# OurEDA-P1K_zynq.net
KiCad netlist of a schematic drawn in Altium Designer
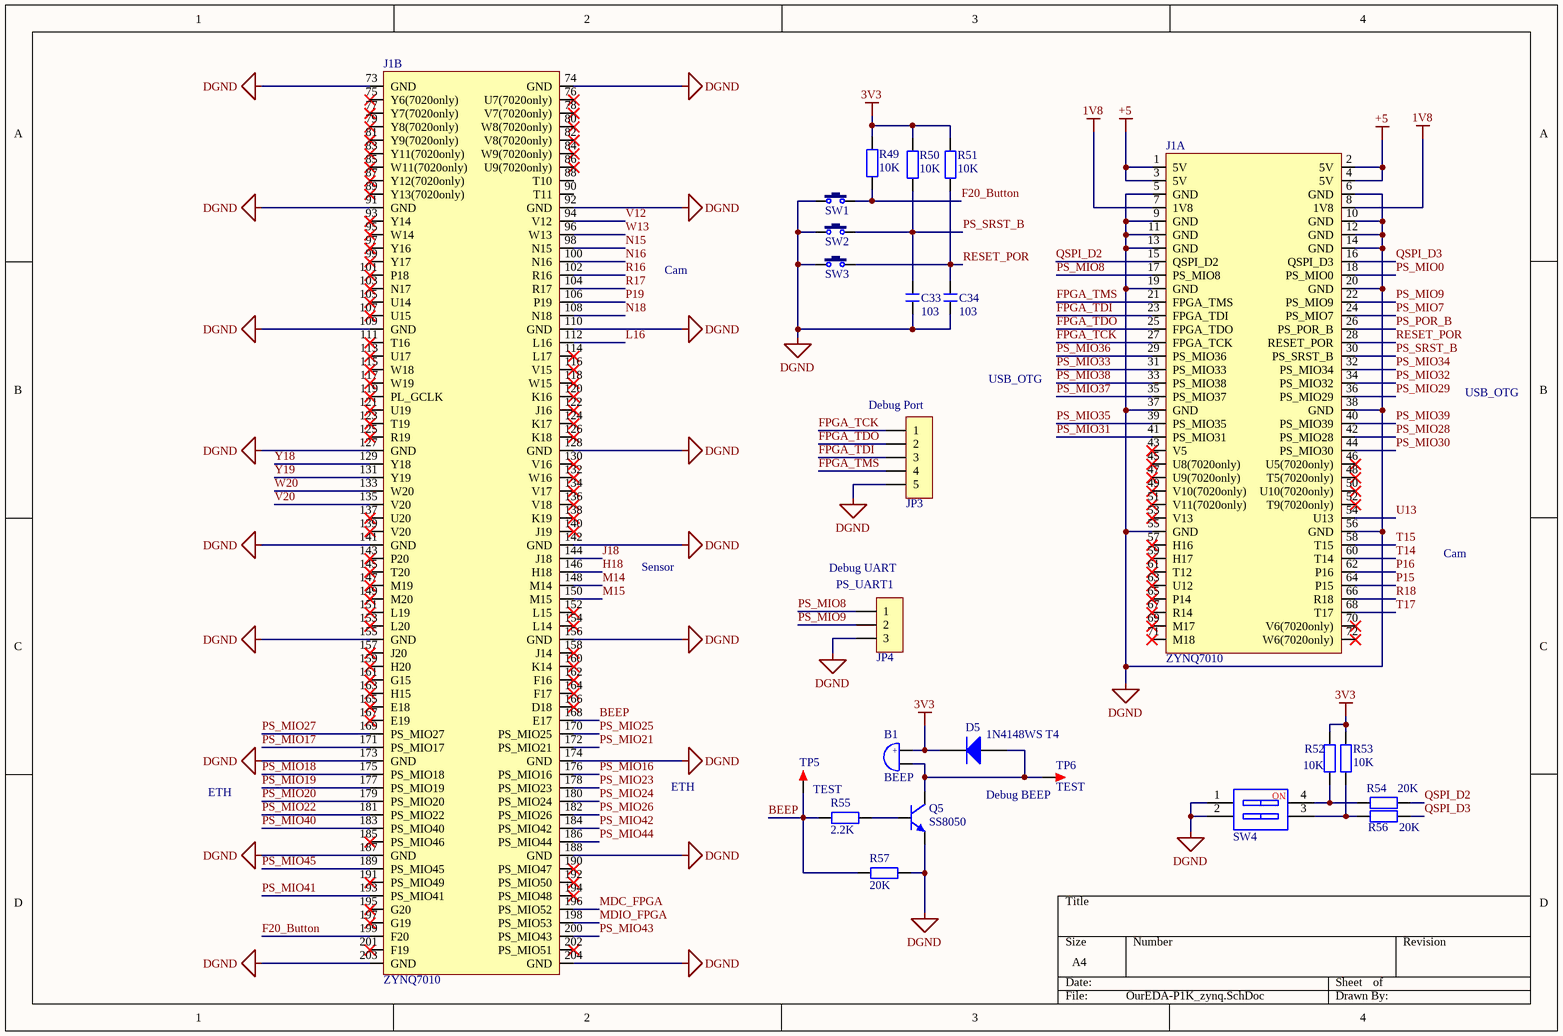
[diagram p0: OurEDA-P1K_zynq.SchDoc]

(export (version "E")
  (design (tool "Eeschema 10.0.6"))
  (components
    (comp (ref "B1")
      (value "BEEP")
      (footprint "BEEP 5x9x5.5")
      (description "蜂鸣器")
      (libsource (lib "蜂鸣器") (part "BEEP"))
    )
    (comp (ref "C33")
      (value "103")
      (footprint "C 0603_L")
      (description "无极性贴片电容")
      (fields (field (name "版权归属") "源创客"))
      (libsource (lib "3.1   - 电阻-电容-电感") (part "C"))
    )
    (comp (ref "C34")
      (value "103")
      (footprint "C 0603_L")
      (description "无极性贴片电容")
      (fields (field (name "版权归属") "源创客"))
      (libsource (lib "3.1   - 电阻-电容-电感") (part "C"))
    )
    (comp (ref "D5")
      (value "1N4148WS T4")
      (footprint "SOD-323")
      (description "二极管")
      (libsource (lib "Miscellaneous Devices LC") (part "SOD-323 1N4148WS T4"))
    )
    (comp (ref "J1")
      (value "ZYNQ7010")
      (footprint "DDR3_sodimm_Pin204")
      (libsource (lib "MySchLib") (part "DDR3_sodimm_Pin204"))
    )
    (comp (ref "JP3")
      (value "HDR-1X5")
      (footprint "MX 1.25-LS-5P")
      (description "5P接插件")
      (fields (field (name "版权归属") "源创客"))
      (libsource (lib "4.2   - 接插件-脚距1.25") (part "Header 5"))
    )
    (comp (ref "JP4")
      (value "HDR-1X3")
      (footprint "MX 1.25-LS-3P")
      (description "3P接插件")
      (fields (field (name "版权归属") "源创客"))
      (libsource (lib "4.2   - 接插件-脚距1.25") (part "Header 3"))
    )
    (comp (ref "Q5")
      (value "SS8050")
      (footprint "SOT23-3N")
      (description "高频放大-NPN型")
      (fields (field (name "版权归属") "源创客"))
      (libsource (lib "6.2   - 三极管") (part "8050-SMD"))
    )
    (comp (ref "R49")
      (value "10K")
      (footprint "R 0603_L")
      (description "贴片电阻")
      (fields (field (name "版权归属") "源创客"))
      (libsource (lib "3.1   - 电阻-电容-电感") (part "R"))
    )
    (comp (ref "R50")
      (value "10K")
      (footprint "R 0603_L")
      (description "贴片电阻")
      (fields (field (name "版权归属") "源创客"))
      (libsource (lib "3.1   - 电阻-电容-电感") (part "R"))
    )
    (comp (ref "R51")
      (value "10K")
      (footprint "R 0603_L")
      (description "贴片电阻")
      (fields (field (name "版权归属") "源创客"))
      (libsource (lib "3.1   - 电阻-电容-电感") (part "R"))
    )
    (comp (ref "R52")
      (value "10K")
      (footprint "R 0603_L")
      (description "贴片电阻")
      (fields (field (name "版权归属") "源创客"))
      (libsource (lib "3.1   - 电阻-电容-电感") (part "R"))
    )
    (comp (ref "R53")
      (value "10K")
      (footprint "R 0603_L")
      (description "贴片电阻")
      (fields (field (name "版权归属") "源创客"))
      (libsource (lib "3.1   - 电阻-电容-电感") (part "R"))
    )
    (comp (ref "R54")
      (value "20K")
      (footprint "R 0603_L")
      (description "贴片电阻")
      (fields (field (name "版权归属") "源创客"))
      (libsource (lib "3.1   - 电阻-电容-电感") (part "R"))
    )
    (comp (ref "R55")
      (value "2.2K")
      (footprint "R 0603_L")
      (description "贴片电阻")
      (fields (field (name "版权归属") "源创客"))
      (libsource (lib "3.1   - 电阻-电容-电感") (part "R"))
    )
    (comp (ref "R56")
      (value "20K")
      (footprint "R 0603_L")
      (description "贴片电阻")
      (fields (field (name "版权归属") "源创客"))
      (libsource (lib "3.1   - 电阻-电容-电感") (part "R"))
    )
    (comp (ref "R57")
      (value "20K")
      (footprint "R 0603_L")
      (description "贴片电阻")
      (fields (field (name "版权归属") "源创客"))
      (libsource (lib "3.1   - 电阻-电容-电感") (part "R"))
    )
    (comp (ref "SW1")
      (value "3x6x5")
      (footprint "TSW SMD-3*6*2.5")
      (description "3x6轻触开关")
      (fields (field (name "版权归属") "源创客"))
      (libsource (lib "5.1   - 按键-开关") (part "TSW 3x6"))
    )
    (comp (ref "SW2")
      (value "3x6x5")
      (footprint "TSW SMD-3*6*2.5")
      (description "3x6轻触开关")
      (fields (field (name "版权归属") "源创客"))
      (libsource (lib "5.1   - 按键-开关") (part "TSW 3x6"))
    )
    (comp (ref "SW3")
      (value "3x6x5")
      (footprint "TSW SMD-3*6*2.5")
      (description "3x6轻触开关")
      (fields (field (name "版权归属") "源创客"))
      (libsource (lib "5.1   - 按键-开关") (part "TSW 3x6"))
    )
    (comp (ref "SW4")
      (value "CSW-2P")
      (footprint "CSW1.27 SMD-2P")
      (description "2路编码开关")
      (fields (field (name "版权归属") "源创客"))
      (libsource (lib "5.1   - 按键-开关") (part "CSW-2P"))
    )
    (comp (ref "TP5")
      (value "TEST")
      (footprint "TEST 1")
      (description "测试点")
      (fields (field (name "版权归属") "源创客"))
      (libsource (lib "15.1 - 未分类器件") (part "TEST"))
    )
    (comp (ref "TP6")
      (value "TEST")
      (footprint "TEST 1")
      (description "测试点")
      (fields (field (name "版权归属") "源创客"))
      (libsource (lib "15.1 - 未分类器件") (part "TEST"))
    )
  )
  (nets
    (net (code "1") (name "+5") (class "Default")
      (node (ref "J1") (pin "1") (pinfunction "5V_1") (pintype "passive"))
      (node (ref "J1") (pin "2") (pinfunction "5V_2") (pintype "passive"))
      (node (ref "J1") (pin "3") (pinfunction "5V_3") (pintype "passive"))
      (node (ref "J1") (pin "4") (pinfunction "5V_4") (pintype "passive"))
    )
    (net (code "2") (name "/BEEP") (class "Default")
      (node (ref "J1") (pin "168") (pinfunction "E17_168") (pintype "passive"))
      (node (ref "R55") (pin "2") (pinfunction "2_2") (pintype "passive"))
      (node (ref "R57") (pin "1") (pinfunction "1_1") (pintype "passive"))
      (node (ref "TP5") (pin "1") (pinfunction "1_1") (pintype "passive"))
    )
    (net (code "3") (name "/F20_Button") (class "Default")
      (node (ref "J1") (pin "199") (pinfunction "F20_199") (pintype "passive"))
      (node (ref "R49") (pin "1") (pinfunction "1_1") (pintype "passive"))
      (node (ref "SW1") (pin "2") (pinfunction "2_2") (pintype "passive"))
    )
    (net (code "4") (name "/FPGA_TCK") (class "Default")
      (node (ref "J1") (pin "27") (pinfunction "FPGA_TCK_27") (pintype "passive"))
      (node (ref "JP3") (pin "1") (pinfunction "1_1") (pintype "passive"))
    )
    (net (code "5") (name "/FPGA_TDI") (class "Default")
      (node (ref "J1") (pin "23") (pinfunction "FPGA_TDI_23") (pintype "passive"))
      (node (ref "JP3") (pin "3") (pinfunction "3_3") (pintype "passive"))
    )
    (net (code "6") (name "/FPGA_TDO") (class "Default")
      (node (ref "J1") (pin "25") (pinfunction "FPGA_TDO_25") (pintype "passive"))
      (node (ref "JP3") (pin "2") (pinfunction "2_2") (pintype "passive"))
    )
    (net (code "7") (name "/FPGA_TMS") (class "Default")
      (node (ref "J1") (pin "21") (pinfunction "FPGA_TMS_21") (pintype "passive"))
      (node (ref "JP3") (pin "4") (pinfunction "4_4") (pintype "passive"))
    )
    (net (code "8") (name "/H18") (class "Default")
      (node (ref "J1") (pin "146") (pinfunction "H18_146") (pintype "passive"))
    )
    (net (code "9") (name "/J18") (class "Default")
      (node (ref "J1") (pin "144") (pinfunction "J18_144") (pintype "passive"))
    )
    (net (code "10") (name "/L16") (class "Default")
      (node (ref "J1") (pin "112") (pinfunction "L16_112") (pintype "passive"))
    )
    (net (code "11") (name "/M14") (class "Default")
      (node (ref "J1") (pin "148") (pinfunction "M14_148") (pintype "passive"))
    )
    (net (code "12") (name "/M15") (class "Default")
      (node (ref "J1") (pin "150") (pinfunction "M15_150") (pintype "passive"))
    )
    (net (code "13") (name "/MDC_FPGA") (class "Default")
      (node (ref "J1") (pin "196") (pinfunction "PS_MIO52_196") (pintype "passive"))
    )
    (net (code "14") (name "/MDIO_FPGA") (class "Default")
      (node (ref "J1") (pin "198") (pinfunction "PS_MIO53_198") (pintype "passive"))
    )
    (net (code "15") (name "/N15") (class "Default")
      (node (ref "J1") (pin "98") (pinfunction "N15_98") (pintype "passive"))
    )
    (net (code "16") (name "/N16") (class "Default")
      (node (ref "J1") (pin "100") (pinfunction "N16_100") (pintype "passive"))
    )
    (net (code "17") (name "/N18") (class "Default")
      (node (ref "J1") (pin "108") (pinfunction "N18_108") (pintype "passive"))
    )
    (net (code "18") (name "/P15") (class "Default")
      (node (ref "J1") (pin "64") (pinfunction "P15_64") (pintype "passive"))
    )
    (net (code "19") (name "/P16") (class "Default")
      (node (ref "J1") (pin "62") (pinfunction "P16_62") (pintype "passive"))
    )
    (net (code "20") (name "/P19") (class "Default")
      (node (ref "J1") (pin "106") (pinfunction "P19_106") (pintype "passive"))
    )
    (net (code "21") (name "/PS_MIO0") (class "Default")
      (node (ref "J1") (pin "18") (pinfunction "PS_MIO0_18") (pintype "passive"))
    )
    (net (code "22") (name "/PS_MIO7") (class "Default")
      (node (ref "J1") (pin "24") (pinfunction "PS_MIO7_24") (pintype "passive"))
    )
    (net (code "23") (name "/PS_MIO8") (class "Default")
      (node (ref "J1") (pin "17") (pinfunction "PS_MIO8_17") (pintype "passive"))
      (node (ref "JP4") (pin "1") (pinfunction "1_1") (pintype "passive"))
    )
    (net (code "24") (name "/PS_MIO9") (class "Default")
      (node (ref "J1") (pin "22") (pinfunction "PS_MIO9_22") (pintype "passive"))
      (node (ref "JP4") (pin "2") (pinfunction "2_2") (pintype "passive"))
    )
    (net (code "25") (name "/PS_MIO16") (class "Default")
      (node (ref "J1") (pin "176") (pinfunction "PS_MIO16_176") (pintype "passive"))
    )
    (net (code "26") (name "/PS_MIO17") (class "Default")
      (node (ref "J1") (pin "171") (pinfunction "PS_MIO17_171") (pintype "passive"))
    )
    (net (code "27") (name "/PS_MIO18") (class "Default")
      (node (ref "J1") (pin "175") (pinfunction "PS_MIO18_175") (pintype "passive"))
    )
    (net (code "28") (name "/PS_MIO19") (class "Default")
      (node (ref "J1") (pin "177") (pinfunction "PS_MIO19_177") (pintype "passive"))
    )
    (net (code "29") (name "/PS_MIO20") (class "Default")
      (node (ref "J1") (pin "179") (pinfunction "PS_MIO20_179") (pintype "passive"))
    )
    (net (code "30") (name "/PS_MIO21") (class "Default")
      (node (ref "J1") (pin "172") (pinfunction "PS_MIO21_172") (pintype "passive"))
    )
    (net (code "31") (name "/PS_MIO22") (class "Default")
      (node (ref "J1") (pin "181") (pinfunction "PS_MIO22_181") (pintype "passive"))
    )
    (net (code "32") (name "/PS_MIO23") (class "Default")
      (node (ref "J1") (pin "178") (pinfunction "PS_MIO23_178") (pintype "passive"))
    )
    (net (code "33") (name "/PS_MIO24") (class "Default")
      (node (ref "J1") (pin "180") (pinfunction "PS_MIO24_180") (pintype "passive"))
    )
    (net (code "34") (name "/PS_MIO25") (class "Default")
      (node (ref "J1") (pin "170") (pinfunction "PS_MIO25_170") (pintype "passive"))
    )
    (net (code "35") (name "/PS_MIO26") (class "Default")
      (node (ref "J1") (pin "182") (pinfunction "PS_MIO26_182") (pintype "passive"))
    )
    (net (code "36") (name "/PS_MIO27") (class "Default")
      (node (ref "J1") (pin "169") (pinfunction "PS_MIO27_169") (pintype "passive"))
    )
    (net (code "37") (name "/PS_MIO28") (class "Default")
      (node (ref "J1") (pin "42") (pinfunction "PS_MIO28_42") (pintype "passive"))
    )
    (net (code "38") (name "/PS_MIO29") (class "Default")
      (node (ref "J1") (pin "36") (pinfunction "PS_MIO29_36") (pintype "passive"))
    )
    (net (code "39") (name "/PS_MIO30") (class "Default")
      (node (ref "J1") (pin "44") (pinfunction "PS_MIO30_44") (pintype "passive"))
    )
    (net (code "40") (name "/PS_MIO31") (class "Default")
      (node (ref "J1") (pin "41") (pinfunction "PS_MIO31_41") (pintype "passive"))
    )
    (net (code "41") (name "/PS_MIO32") (class "Default")
      (node (ref "J1") (pin "34") (pinfunction "PS_MIO32_34") (pintype "passive"))
    )
    (net (code "42") (name "/PS_MIO33") (class "Default")
      (node (ref "J1") (pin "31") (pinfunction "PS_MIO33_31") (pintype "passive"))
    )
    (net (code "43") (name "/PS_MIO34") (class "Default")
      (node (ref "J1") (pin "32") (pinfunction "PS_MIO34_32") (pintype "passive"))
    )
    (net (code "44") (name "/PS_MIO35") (class "Default")
      (node (ref "J1") (pin "39") (pinfunction "PS_MIO35_39") (pintype "passive"))
    )
    (net (code "45") (name "/PS_MIO36") (class "Default")
      (node (ref "J1") (pin "29") (pinfunction "PS_MIO36_29") (pintype "passive"))
    )
    (net (code "46") (name "/PS_MIO37") (class "Default")
      (node (ref "J1") (pin "35") (pinfunction "PS_MIO37_35") (pintype "passive"))
    )
    (net (code "47") (name "/PS_MIO38") (class "Default")
      (node (ref "J1") (pin "33") (pinfunction "PS_MIO38_33") (pintype "passive"))
    )
    (net (code "48") (name "/PS_MIO39") (class "Default")
      (node (ref "J1") (pin "40") (pinfunction "PS_MIO39_40") (pintype "passive"))
    )
    (net (code "49") (name "/PS_MIO40") (class "Default")
      (node (ref "J1") (pin "183") (pinfunction "PS_MIO40_183") (pintype "passive"))
    )
    (net (code "50") (name "/PS_MIO41") (class "Default")
      (node (ref "J1") (pin "193") (pinfunction "PS_MIO41_193") (pintype "passive"))
    )
    (net (code "51") (name "/PS_MIO42") (class "Default")
      (node (ref "J1") (pin "184") (pinfunction "PS_MIO42_184") (pintype "passive"))
    )
    (net (code "52") (name "/PS_MIO43") (class "Default")
      (node (ref "J1") (pin "200") (pinfunction "PS_MIO43_200") (pintype "passive"))
    )
    (net (code "53") (name "/PS_MIO44") (class "Default")
      (node (ref "J1") (pin "186") (pinfunction "PS_MIO44_186") (pintype "passive"))
    )
    (net (code "54") (name "/PS_MIO45") (class "Default")
      (node (ref "J1") (pin "189") (pinfunction "PS_MIO45_189") (pintype "passive"))
    )
    (net (code "55") (name "/PS_POR_B") (class "Default")
      (node (ref "J1") (pin "26") (pinfunction "PS_POR_B_26") (pintype "passive"))
    )
    (net (code "56") (name "/PS_SRST_B") (class "Default")
      (node (ref "C33") (pin "2") (pinfunction "2_2") (pintype "passive"))
      (node (ref "J1") (pin "30") (pinfunction "PS_SRST_B_30") (pintype "passive"))
      (node (ref "R50") (pin "1") (pinfunction "1_1") (pintype "passive"))
      (node (ref "SW2") (pin "2") (pinfunction "2_2") (pintype "passive"))
    )
    (net (code "57") (name "/QSPI_D2") (class "Default")
      (node (ref "J1") (pin "15") (pinfunction "QSPI_D2_15") (pintype "passive"))
      (node (ref "R54") (pin "2") (pinfunction "2_2") (pintype "passive"))
    )
    (net (code "58") (name "/QSPI_D3") (class "Default")
      (node (ref "J1") (pin "16") (pinfunction "QSPI_D3_16") (pintype "passive"))
      (node (ref "R56") (pin "2") (pinfunction "2_2") (pintype "passive"))
    )
    (net (code "59") (name "/R16") (class "Default")
      (node (ref "J1") (pin "102") (pinfunction "R16_102") (pintype "passive"))
    )
    (net (code "60") (name "/R17") (class "Default")
      (node (ref "J1") (pin "104") (pinfunction "R17_104") (pintype "passive"))
    )
    (net (code "61") (name "/R18") (class "Default")
      (node (ref "J1") (pin "66") (pinfunction "R18_66") (pintype "passive"))
    )
    (net (code "62") (name "/RESET_POR") (class "Default")
      (node (ref "C34") (pin "2") (pinfunction "2_2") (pintype "passive"))
      (node (ref "J1") (pin "28") (pinfunction "RESET_POR_28") (pintype "passive"))
      (node (ref "R51") (pin "1") (pinfunction "1_1") (pintype "passive"))
      (node (ref "SW3") (pin "2") (pinfunction "2_2") (pintype "passive"))
    )
    (net (code "63") (name "/T14") (class "Default")
      (node (ref "J1") (pin "60") (pinfunction "T14_60") (pintype "passive"))
    )
    (net (code "64") (name "/T15") (class "Default")
      (node (ref "J1") (pin "58") (pinfunction "T15_58") (pintype "passive"))
    )
    (net (code "65") (name "/T17") (class "Default")
      (node (ref "J1") (pin "68") (pinfunction "T17_68") (pintype "passive"))
    )
    (net (code "66") (name "/U13") (class "Default")
      (node (ref "J1") (pin "54") (pinfunction "U13_54") (pintype "passive"))
    )
    (net (code "67") (name "/V12") (class "Default")
      (node (ref "J1") (pin "94") (pinfunction "V12_94") (pintype "passive"))
    )
    (net (code "68") (name "/V20") (class "Default")
      (node (ref "J1") (pin "135") (pinfunction "V20_135") (pintype "passive"))
    )
    (net (code "69") (name "/W13") (class "Default")
      (node (ref "J1") (pin "96") (pinfunction "W13_96") (pintype "passive"))
    )
    (net (code "70") (name "/W20") (class "Default")
      (node (ref "J1") (pin "133") (pinfunction "W20_133") (pintype "passive"))
    )
    (net (code "71") (name "/Y18") (class "Default")
      (node (ref "J1") (pin "129") (pinfunction "Y18_129") (pintype "passive"))
    )
    (net (code "72") (name "/Y19") (class "Default")
      (node (ref "J1") (pin "131") (pinfunction "Y19_131") (pintype "passive"))
    )
    (net (code "73") (name "1V8") (class "Default")
      (node (ref "J1") (pin "7") (pinfunction "1V8_7") (pintype "passive"))
      (node (ref "J1") (pin "8") (pinfunction "1V8_8") (pintype "passive"))
    )
    (net (code "74") (name "3V3") (class "Default")
      (node (ref "B1") (pin "1") (pinfunction "1_1") (pintype "passive"))
      (node (ref "D5") (pin "2") (pinfunction "K_2") (pintype "passive"))
      (node (ref "R49") (pin "2") (pinfunction "2_2") (pintype "passive"))
      (node (ref "R50") (pin "2") (pinfunction "2_2") (pintype "passive"))
      (node (ref "R51") (pin "2") (pinfunction "2_2") (pintype "passive"))
      (node (ref "R52") (pin "2") (pinfunction "2_2") (pintype "passive"))
      (node (ref "R53") (pin "2") (pinfunction "2_2") (pintype "passive"))
    )
    (net (code "75") (name "DGND") (class "Default")
      (node (ref "C33") (pin "1") (pinfunction "1_1") (pintype "passive"))
      (node (ref "C34") (pin "1") (pinfunction "1_1") (pintype "passive"))
      (node (ref "J1") (pin "10") (pinfunction "GND_10") (pintype "passive"))
      (node (ref "J1") (pin "109") (pinfunction "GND_109") (pintype "passive"))
      (node (ref "J1") (pin "11") (pinfunction "GND_11") (pintype "passive"))
      (node (ref "J1") (pin "110") (pinfunction "GND_110") (pintype "passive"))
      (node (ref "J1") (pin "12") (pinfunction "GND_12") (pintype "passive"))
      (node (ref "J1") (pin "127") (pinfunction "GND_127") (pintype "passive"))
      (node (ref "J1") (pin "128") (pinfunction "GND_128") (pintype "passive"))
      (node (ref "J1") (pin "13") (pinfunction "GND_13") (pintype "passive"))
      (node (ref "J1") (pin "14") (pinfunction "GND_14") (pintype "passive"))
      (node (ref "J1") (pin "141") (pinfunction "GND_141") (pintype "passive"))
      (node (ref "J1") (pin "142") (pinfunction "GND_142") (pintype "passive"))
      (node (ref "J1") (pin "155") (pinfunction "GND_155") (pintype "passive"))
      (node (ref "J1") (pin "156") (pinfunction "GND_156") (pintype "passive"))
      (node (ref "J1") (pin "173") (pinfunction "GND_173") (pintype "passive"))
      (node (ref "J1") (pin "174") (pinfunction "GND_174") (pintype "passive"))
      (node (ref "J1") (pin "187") (pinfunction "GND_187") (pintype "passive"))
      (node (ref "J1") (pin "188") (pinfunction "GND_188") (pintype "passive"))
      (node (ref "J1") (pin "19") (pinfunction "GND_19") (pintype "passive"))
      (node (ref "J1") (pin "20") (pinfunction "GND_20") (pintype "passive"))
      (node (ref "J1") (pin "203") (pinfunction "GND_203") (pintype "passive"))
      (node (ref "J1") (pin "204") (pinfunction "GND_204") (pintype "passive"))
      (node (ref "J1") (pin "37") (pinfunction "GND_37") (pintype "passive"))
      (node (ref "J1") (pin "38") (pinfunction "GND_38") (pintype "passive"))
      (node (ref "J1") (pin "5") (pinfunction "GND_5") (pintype "passive"))
      (node (ref "J1") (pin "55") (pinfunction "GND_55") (pintype "passive"))
      (node (ref "J1") (pin "56") (pinfunction "GND_56") (pintype "passive"))
      (node (ref "J1") (pin "6") (pinfunction "GND_6") (pintype "passive"))
      (node (ref "J1") (pin "73") (pinfunction "GND_73") (pintype "passive"))
      (node (ref "J1") (pin "74") (pinfunction "GND_74") (pintype "passive"))
      (node (ref "J1") (pin "9") (pinfunction "GND_9") (pintype "passive"))
      (node (ref "J1") (pin "91") (pinfunction "GND_91") (pintype "passive"))
      (node (ref "J1") (pin "92") (pinfunction "GND_92") (pintype "passive"))
      (node (ref "JP3") (pin "5") (pinfunction "5_5") (pintype "passive"))
      (node (ref "JP4") (pin "3") (pinfunction "3_3") (pintype "passive"))
      (node (ref "Q5") (pin "2") (pinfunction "E_2") (pintype "passive"))
      (node (ref "R57") (pin "2") (pinfunction "2_2") (pintype "passive"))
      (node (ref "SW1") (pin "1") (pinfunction "1_1") (pintype "passive"))
      (node (ref "SW2") (pin "1") (pinfunction "1_1") (pintype "passive"))
      (node (ref "SW3") (pin "1") (pinfunction "1_1") (pintype "passive"))
      (node (ref "SW4") (pin "1") (pinfunction "1_1") (pintype "passive"))
      (node (ref "SW4") (pin "2") (pinfunction "2_2") (pintype "passive"))
    )
    (net (code "76") (name "Net-(D5-A)") (class "Default")
      (node (ref "B1") (pin "2") (pinfunction "2_2") (pintype "passive"))
      (node (ref "D5") (pin "1") (pinfunction "A_1") (pintype "passive"))
      (node (ref "Q5") (pin "3") (pinfunction "C_3") (pintype "passive"))
      (node (ref "TP6") (pin "1") (pinfunction "1_1") (pintype "passive"))
    )
    (net (code "77") (name "Net-(Q5-B)") (class "Default")
      (node (ref "Q5") (pin "1") (pinfunction "B_1") (pintype "passive"))
      (node (ref "R55") (pin "1") (pinfunction "1_1") (pintype "passive"))
    )
    (net (code "78") (name "Net-(R52-Pad1)") (class "Default")
      (node (ref "R52") (pin "1") (pinfunction "1_1") (pintype "passive"))
      (node (ref "R54") (pin "1") (pinfunction "1_1") (pintype "passive"))
      (node (ref "SW4") (pin "4") (pinfunction "4_4") (pintype "passive"))
    )
    (net (code "79") (name "Net-(R53-Pad1)") (class "Default")
      (node (ref "R53") (pin "1") (pinfunction "1_1") (pintype "passive"))
      (node (ref "R56") (pin "1") (pinfunction "1_1") (pintype "passive"))
      (node (ref "SW4") (pin "3") (pinfunction "3_3") (pintype "passive"))
    )
    (net (code "80") (name "unconnected-(J1A-H16-Pad57)") (class "Default")
      (node (ref "J1") (pin "57") (pinfunction "H16_57") (pintype "passive+no_connect"))
    )
    (net (code "81") (name "unconnected-(J1A-H17-Pad59)") (class "Default")
      (node (ref "J1") (pin "59") (pinfunction "H17_59") (pintype "passive+no_connect"))
    )
    (net (code "82") (name "unconnected-(J1A-M17-Pad69)") (class "Default")
      (node (ref "J1") (pin "69") (pinfunction "M17_69") (pintype "passive+no_connect"))
    )
    (net (code "83") (name "unconnected-(J1A-M18-Pad71)") (class "Default")
      (node (ref "J1") (pin "71") (pinfunction "M18_71") (pintype "passive+no_connect"))
    )
    (net (code "84") (name "unconnected-(J1A-P14-Pad65)") (class "Default")
      (node (ref "J1") (pin "65") (pinfunction "P14_65") (pintype "passive+no_connect"))
    )
    (net (code "85") (name "unconnected-(J1A-R14-Pad67)") (class "Default")
      (node (ref "J1") (pin "67") (pinfunction "R14_67") (pintype "passive+no_connect"))
    )
    (net (code "86") (name "unconnected-(J1A-T5(7020only)-Pad48)") (class "Default")
      (node (ref "J1") (pin "48") (pinfunction "T5(7020only)_48") (pintype "passive+no_connect"))
    )
    (net (code "87") (name "unconnected-(J1A-T9(7020only)-Pad52)") (class "Default")
      (node (ref "J1") (pin "52") (pinfunction "T9(7020only)_52") (pintype "passive+no_connect"))
    )
    (net (code "88") (name "unconnected-(J1A-T12-Pad61)") (class "Default")
      (node (ref "J1") (pin "61") (pinfunction "T12_61") (pintype "passive+no_connect"))
    )
    (net (code "89") (name "unconnected-(J1A-U5(7020only)-Pad46)") (class "Default")
      (node (ref "J1") (pin "46") (pinfunction "U5(7020only)_46") (pintype "passive+no_connect"))
    )
    (net (code "90") (name "unconnected-(J1A-U8(7020only)-Pad45)") (class "Default")
      (node (ref "J1") (pin "45") (pinfunction "U8(7020only)_45") (pintype "passive+no_connect"))
    )
    (net (code "91") (name "unconnected-(J1A-U9(7020only)-Pad47)") (class "Default")
      (node (ref "J1") (pin "47") (pinfunction "U9(7020only)_47") (pintype "passive+no_connect"))
    )
    (net (code "92") (name "unconnected-(J1A-U10(7020only)-Pad50)") (class "Default")
      (node (ref "J1") (pin "50") (pinfunction "U10(7020only)_50") (pintype "passive+no_connect"))
    )
    (net (code "93") (name "unconnected-(J1A-U12-Pad63)") (class "Default")
      (node (ref "J1") (pin "63") (pinfunction "U12_63") (pintype "passive+no_connect"))
    )
    (net (code "94") (name "unconnected-(J1A-V5-Pad43)") (class "Default")
      (node (ref "J1") (pin "43") (pinfunction "V5_43") (pintype "passive+no_connect"))
    )
    (net (code "95") (name "unconnected-(J1A-V6(7020only)-Pad70)") (class "Default")
      (node (ref "J1") (pin "70") (pinfunction "V6(7020only)_70") (pintype "passive+no_connect"))
    )
    (net (code "96") (name "unconnected-(J1A-V10(7020only)-Pad49)") (class "Default")
      (node (ref "J1") (pin "49") (pinfunction "V10(7020only)_49") (pintype "passive+no_connect"))
    )
    (net (code "97") (name "unconnected-(J1A-V11(7020only)-Pad51)") (class "Default")
      (node (ref "J1") (pin "51") (pinfunction "V11(7020only)_51") (pintype "passive+no_connect"))
    )
    (net (code "98") (name "unconnected-(J1A-V13-Pad53)") (class "Default")
      (node (ref "J1") (pin "53") (pinfunction "V13_53") (pintype "passive+no_connect"))
    )
    (net (code "99") (name "unconnected-(J1A-W6(7020only)-Pad72)") (class "Default")
      (node (ref "J1") (pin "72") (pinfunction "W6(7020only)_72") (pintype "passive+no_connect"))
    )
    (net (code "100") (name "unconnected-(J1B-D18-Pad166)") (class "Default")
      (node (ref "J1") (pin "166") (pinfunction "D18_166") (pintype "passive+no_connect"))
    )
    (net (code "101") (name "unconnected-(J1B-E18-Pad165)") (class "Default")
      (node (ref "J1") (pin "165") (pinfunction "E18_165") (pintype "passive+no_connect"))
    )
    (net (code "102") (name "unconnected-(J1B-E19-Pad167)") (class "Default")
      (node (ref "J1") (pin "167") (pinfunction "E19_167") (pintype "passive+no_connect"))
    )
    (net (code "103") (name "unconnected-(J1B-F16-Pad162)") (class "Default")
      (node (ref "J1") (pin "162") (pinfunction "F16_162") (pintype "passive+no_connect"))
    )
    (net (code "104") (name "unconnected-(J1B-F17-Pad164)") (class "Default")
      (node (ref "J1") (pin "164") (pinfunction "F17_164") (pintype "passive+no_connect"))
    )
    (net (code "105") (name "unconnected-(J1B-F19-Pad201)") (class "Default")
      (node (ref "J1") (pin "201") (pinfunction "F19_201") (pintype "passive+no_connect"))
    )
    (net (code "106") (name "unconnected-(J1B-G15-Pad161)") (class "Default")
      (node (ref "J1") (pin "161") (pinfunction "G15_161") (pintype "passive+no_connect"))
    )
    (net (code "107") (name "unconnected-(J1B-G19-Pad197)") (class "Default")
      (node (ref "J1") (pin "197") (pinfunction "G19_197") (pintype "passive+no_connect"))
    )
    (net (code "108") (name "unconnected-(J1B-G20-Pad195)") (class "Default")
      (node (ref "J1") (pin "195") (pinfunction "G20_195") (pintype "passive+no_connect"))
    )
    (net (code "109") (name "unconnected-(J1B-H15-Pad163)") (class "Default")
      (node (ref "J1") (pin "163") (pinfunction "H15_163") (pintype "passive+no_connect"))
    )
    (net (code "110") (name "unconnected-(J1B-H20-Pad159)") (class "Default")
      (node (ref "J1") (pin "159") (pinfunction "H20_159") (pintype "passive+no_connect"))
    )
    (net (code "111") (name "unconnected-(J1B-J14-Pad158)") (class "Default")
      (node (ref "J1") (pin "158") (pinfunction "J14_158") (pintype "passive+no_connect"))
    )
    (net (code "112") (name "unconnected-(J1B-J16-Pad122)") (class "Default")
      (node (ref "J1") (pin "122") (pinfunction "J16_122") (pintype "passive+no_connect"))
    )
    (net (code "113") (name "unconnected-(J1B-J19-Pad140)") (class "Default")
      (node (ref "J1") (pin "140") (pinfunction "J19_140") (pintype "passive+no_connect"))
    )
    (net (code "114") (name "unconnected-(J1B-J20-Pad157)") (class "Default")
      (node (ref "J1") (pin "157") (pinfunction "J20_157") (pintype "passive+no_connect"))
    )
    (net (code "115") (name "unconnected-(J1B-K14-Pad160)") (class "Default")
      (node (ref "J1") (pin "160") (pinfunction "K14_160") (pintype "passive+no_connect"))
    )
    (net (code "116") (name "unconnected-(J1B-K16-Pad120)") (class "Default")
      (node (ref "J1") (pin "120") (pinfunction "K16_120") (pintype "passive+no_connect"))
    )
    (net (code "117") (name "unconnected-(J1B-K17-Pad124)") (class "Default")
      (node (ref "J1") (pin "124") (pinfunction "K17_124") (pintype "passive+no_connect"))
    )
    (net (code "118") (name "unconnected-(J1B-K18-Pad126)") (class "Default")
      (node (ref "J1") (pin "126") (pinfunction "K18_126") (pintype "passive+no_connect"))
    )
    (net (code "119") (name "unconnected-(J1B-K19-Pad138)") (class "Default")
      (node (ref "J1") (pin "138") (pinfunction "K19_138") (pintype "passive+no_connect"))
    )
    (net (code "120") (name "unconnected-(J1B-L14-Pad154)") (class "Default")
      (node (ref "J1") (pin "154") (pinfunction "L14_154") (pintype "passive+no_connect"))
    )
    (net (code "121") (name "unconnected-(J1B-L15-Pad152)") (class "Default")
      (node (ref "J1") (pin "152") (pinfunction "L15_152") (pintype "passive+no_connect"))
    )
    (net (code "122") (name "unconnected-(J1B-L17-Pad114)") (class "Default")
      (node (ref "J1") (pin "114") (pinfunction "L17_114") (pintype "passive+no_connect"))
    )
    (net (code "123") (name "unconnected-(J1B-L19-Pad151)") (class "Default")
      (node (ref "J1") (pin "151") (pinfunction "L19_151") (pintype "passive+no_connect"))
    )
    (net (code "124") (name "unconnected-(J1B-L20-Pad153)") (class "Default")
      (node (ref "J1") (pin "153") (pinfunction "L20_153") (pintype "passive+no_connect"))
    )
    (net (code "125") (name "unconnected-(J1B-M19-Pad147)") (class "Default")
      (node (ref "J1") (pin "147") (pinfunction "M19_147") (pintype "passive+no_connect"))
    )
    (net (code "126") (name "unconnected-(J1B-M20-Pad149)") (class "Default")
      (node (ref "J1") (pin "149") (pinfunction "M20_149") (pintype "passive+no_connect"))
    )
    (net (code "127") (name "unconnected-(J1B-N17-Pad103)") (class "Default")
      (node (ref "J1") (pin "103") (pinfunction "N17_103") (pintype "passive+no_connect"))
    )
    (net (code "128") (name "unconnected-(J1B-P18-Pad101)") (class "Default")
      (node (ref "J1") (pin "101") (pinfunction "P18_101") (pintype "passive+no_connect"))
    )
    (net (code "129") (name "unconnected-(J1B-P20-Pad143)") (class "Default")
      (node (ref "J1") (pin "143") (pinfunction "P20_143") (pintype "passive+no_connect"))
    )
    (net (code "130") (name "unconnected-(J1B-PL_GCLK-Pad119)") (class "Default")
      (node (ref "J1") (pin "119") (pinfunction "PL_GCLK_119") (pintype "passive+no_connect"))
    )
    (net (code "131") (name "unconnected-(J1B-PS_MIO46-Pad185)") (class "Default")
      (node (ref "J1") (pin "185") (pinfunction "PS_MIO46_185") (pintype "passive+no_connect"))
    )
    (net (code "132") (name "unconnected-(J1B-PS_MIO47-Pad190)") (class "Default")
      (node (ref "J1") (pin "190") (pinfunction "PS_MIO47_190") (pintype "passive+no_connect"))
    )
    (net (code "133") (name "unconnected-(J1B-PS_MIO48-Pad194)") (class "Default")
      (node (ref "J1") (pin "194") (pinfunction "PS_MIO48_194") (pintype "passive+no_connect"))
    )
    (net (code "134") (name "unconnected-(J1B-PS_MIO49-Pad191)") (class "Default")
      (node (ref "J1") (pin "191") (pinfunction "PS_MIO49_191") (pintype "passive+no_connect"))
    )
    (net (code "135") (name "unconnected-(J1B-PS_MIO50-Pad192)") (class "Default")
      (node (ref "J1") (pin "192") (pinfunction "PS_MIO50_192") (pintype "passive+no_connect"))
    )
    (net (code "136") (name "unconnected-(J1B-PS_MIO51-Pad202)") (class "Default")
      (node (ref "J1") (pin "202") (pinfunction "PS_MIO51_202") (pintype "passive+no_connect"))
    )
    (net (code "137") (name "unconnected-(J1B-R19-Pad125)") (class "Default")
      (node (ref "J1") (pin "125") (pinfunction "R19_125") (pintype "passive+no_connect"))
    )
    (net (code "138") (name "unconnected-(J1B-T10-Pad88)") (class "Default")
      (node (ref "J1") (pin "88") (pinfunction "T10_88") (pintype "passive"))
    )
    (net (code "139") (name "unconnected-(J1B-T11-Pad90)") (class "Default")
      (node (ref "J1") (pin "90") (pinfunction "T11_90") (pintype "passive"))
    )
    (net (code "140") (name "unconnected-(J1B-T16-Pad111)") (class "Default")
      (node (ref "J1") (pin "111") (pinfunction "T16_111") (pintype "passive+no_connect"))
    )
    (net (code "141") (name "unconnected-(J1B-T19-Pad123)") (class "Default")
      (node (ref "J1") (pin "123") (pinfunction "T19_123") (pintype "passive+no_connect"))
    )
    (net (code "142") (name "unconnected-(J1B-T20-Pad145)") (class "Default")
      (node (ref "J1") (pin "145") (pinfunction "T20_145") (pintype "passive+no_connect"))
    )
    (net (code "143") (name "unconnected-(J1B-U7(7020only)-Pad76)") (class "Default")
      (node (ref "J1") (pin "76") (pinfunction "U7(7020only)_76") (pintype "passive+no_connect"))
    )
    (net (code "144") (name "unconnected-(J1B-U9(7020only)-Pad86)") (class "Default")
      (node (ref "J1") (pin "86") (pinfunction "U9(7020only)_86") (pintype "passive+no_connect"))
    )
    (net (code "145") (name "unconnected-(J1B-U14-Pad105)") (class "Default")
      (node (ref "J1") (pin "105") (pinfunction "U14_105") (pintype "passive+no_connect"))
    )
    (net (code "146") (name "unconnected-(J1B-U15-Pad107)") (class "Default")
      (node (ref "J1") (pin "107") (pinfunction "U15_107") (pintype "passive+no_connect"))
    )
    (net (code "147") (name "unconnected-(J1B-U17-Pad113)") (class "Default")
      (node (ref "J1") (pin "113") (pinfunction "U17_113") (pintype "passive+no_connect"))
    )
    (net (code "148") (name "unconnected-(J1B-U19-Pad121)") (class "Default")
      (node (ref "J1") (pin "121") (pinfunction "U19_121") (pintype "passive+no_connect"))
    )
    (net (code "149") (name "unconnected-(J1B-U20-Pad137)") (class "Default")
      (node (ref "J1") (pin "137") (pinfunction "U20_137") (pintype "passive+no_connect"))
    )
    (net (code "150") (name "unconnected-(J1B-V7(7020only)-Pad78)") (class "Default")
      (node (ref "J1") (pin "78") (pinfunction "V7(7020only)_78") (pintype "passive+no_connect"))
    )
    (net (code "151") (name "unconnected-(J1B-V8(7020only)-Pad82)") (class "Default")
      (node (ref "J1") (pin "82") (pinfunction "V8(7020only)_82") (pintype "passive+no_connect"))
    )
    (net (code "152") (name "unconnected-(J1B-V15-Pad116)") (class "Default")
      (node (ref "J1") (pin "116") (pinfunction "V15_116") (pintype "passive+no_connect"))
    )
    (net (code "153") (name "unconnected-(J1B-V16-Pad130)") (class "Default")
      (node (ref "J1") (pin "130") (pinfunction "V16_130") (pintype "passive+no_connect"))
    )
    (net (code "154") (name "unconnected-(J1B-V17-Pad134)") (class "Default")
      (node (ref "J1") (pin "134") (pinfunction "V17_134") (pintype "passive+no_connect"))
    )
    (net (code "155") (name "unconnected-(J1B-V18-Pad136)") (class "Default")
      (node (ref "J1") (pin "136") (pinfunction "V18_136") (pintype "passive+no_connect"))
    )
    (net (code "156") (name "unconnected-(J1B-V20-Pad139)") (class "Default")
      (node (ref "J1") (pin "139") (pinfunction "V20_139") (pintype "passive+no_connect"))
    )
    (net (code "157") (name "unconnected-(J1B-W8(7020only)-Pad80)") (class "Default")
      (node (ref "J1") (pin "80") (pinfunction "W8(7020only)_80") (pintype "passive+no_connect"))
    )
    (net (code "158") (name "unconnected-(J1B-W9(7020only)-Pad84)") (class "Default")
      (node (ref "J1") (pin "84") (pinfunction "W9(7020only)_84") (pintype "passive+no_connect"))
    )
    (net (code "159") (name "unconnected-(J1B-W11(7020only)-Pad85)") (class "Default")
      (node (ref "J1") (pin "85") (pinfunction "W11(7020only)_85") (pintype "passive+no_connect"))
    )
    (net (code "160") (name "unconnected-(J1B-W14-Pad95)") (class "Default")
      (node (ref "J1") (pin "95") (pinfunction "W14_95") (pintype "passive+no_connect"))
    )
    (net (code "161") (name "unconnected-(J1B-W15-Pad118)") (class "Default")
      (node (ref "J1") (pin "118") (pinfunction "W15_118") (pintype "passive+no_connect"))
    )
    (net (code "162") (name "unconnected-(J1B-W16-Pad132)") (class "Default")
      (node (ref "J1") (pin "132") (pinfunction "W16_132") (pintype "passive+no_connect"))
    )
    (net (code "163") (name "unconnected-(J1B-W18-Pad115)") (class "Default")
      (node (ref "J1") (pin "115") (pinfunction "W18_115") (pintype "passive+no_connect"))
    )
    (net (code "164") (name "unconnected-(J1B-W19-Pad117)") (class "Default")
      (node (ref "J1") (pin "117") (pinfunction "W19_117") (pintype "passive+no_connect"))
    )
    (net (code "165") (name "unconnected-(J1B-Y6(7020only)-Pad75)") (class "Default")
      (node (ref "J1") (pin "75") (pinfunction "Y6(7020only)_75") (pintype "passive+no_connect"))
    )
    (net (code "166") (name "unconnected-(J1B-Y7(7020only)-Pad77)") (class "Default")
      (node (ref "J1") (pin "77") (pinfunction "Y7(7020only)_77") (pintype "passive+no_connect"))
    )
    (net (code "167") (name "unconnected-(J1B-Y8(7020only)-Pad79)") (class "Default")
      (node (ref "J1") (pin "79") (pinfunction "Y8(7020only)_79") (pintype "passive+no_connect"))
    )
    (net (code "168") (name "unconnected-(J1B-Y9(7020only)-Pad81)") (class "Default")
      (node (ref "J1") (pin "81") (pinfunction "Y9(7020only)_81") (pintype "passive+no_connect"))
    )
    (net (code "169") (name "unconnected-(J1B-Y11(7020only)-Pad83)") (class "Default")
      (node (ref "J1") (pin "83") (pinfunction "Y11(7020only)_83") (pintype "passive+no_connect"))
    )
    (net (code "170") (name "unconnected-(J1B-Y12(7020only)-Pad87)") (class "Default")
      (node (ref "J1") (pin "87") (pinfunction "Y12(7020only)_87") (pintype "passive+no_connect"))
    )
    (net (code "171") (name "unconnected-(J1B-Y13(7020only)-Pad89)") (class "Default")
      (node (ref "J1") (pin "89") (pinfunction "Y13(7020only)_89") (pintype "passive+no_connect"))
    )
    (net (code "172") (name "unconnected-(J1B-Y14-Pad93)") (class "Default")
      (node (ref "J1") (pin "93") (pinfunction "Y14_93") (pintype "passive+no_connect"))
    )
    (net (code "173") (name "unconnected-(J1B-Y16-Pad97)") (class "Default")
      (node (ref "J1") (pin "97") (pinfunction "Y16_97") (pintype "passive+no_connect"))
    )
    (net (code "174") (name "unconnected-(J1B-Y17-Pad99)") (class "Default")
      (node (ref "J1") (pin "99") (pinfunction "Y17_99") (pintype "passive+no_connect"))
    )
  )
)
